# 24x16_RGB_Top.net
KiCad netlist of a schematic drawn in EAGLE
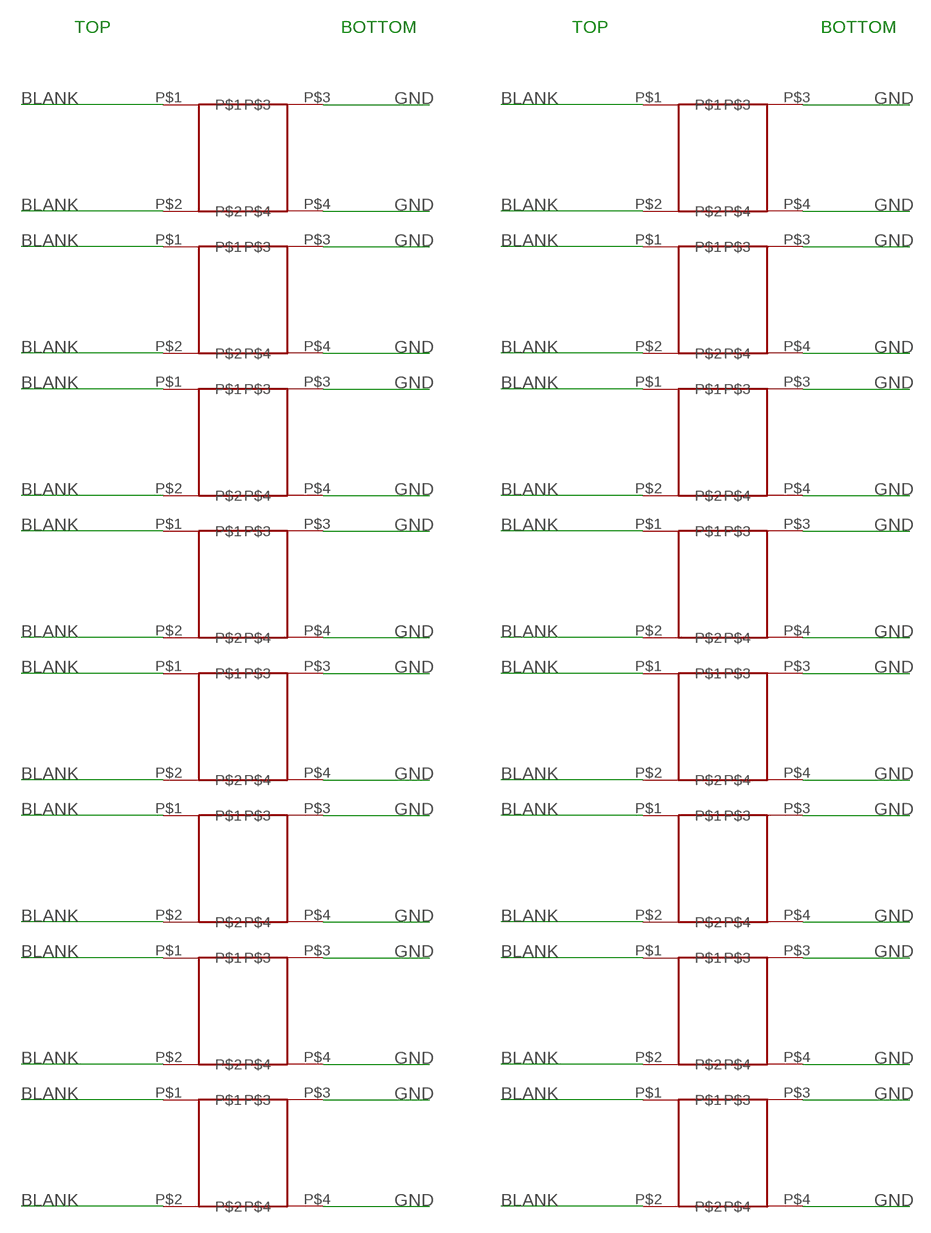
[diagram p0: schematic, sheet 1]
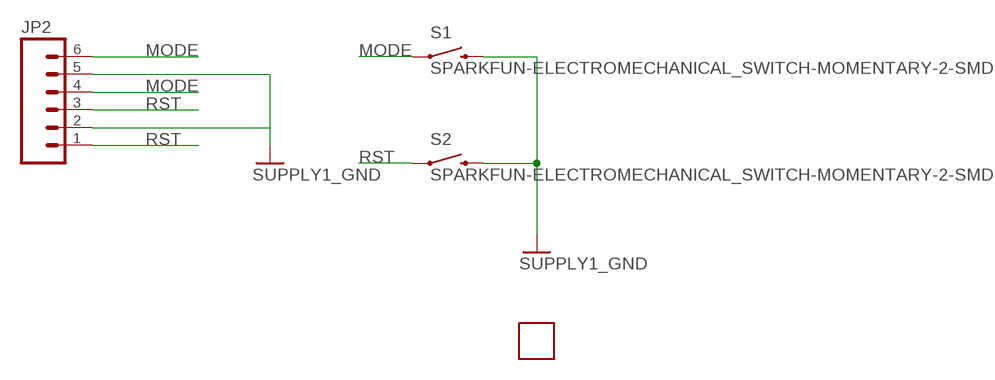
[diagram p1: schematic, sheet 2]

(export (version "E")
  (design (tool "Eeschema 10.0.6"))
  (components
    (comp (ref "SLOT1")
      (value "SLOT")
      (footprint "eagle-import:SLOT")
      (libsource (lib "eagle-import") (part "SLOT"))
    )
    (comp (ref "SLOT2")
      (value "SLOT")
      (footprint "eagle-import:SLOT")
      (libsource (lib "eagle-import") (part "SLOT"))
    )
    (comp (ref "SLOT3")
      (value "SLOT")
      (footprint "eagle-import:SLOT")
      (libsource (lib "eagle-import") (part "SLOT"))
    )
    (comp (ref "SLOT4")
      (value "SLOT")
      (footprint "eagle-import:SLOT")
      (libsource (lib "eagle-import") (part "SLOT"))
    )
    (comp (ref "SLOT5")
      (value "SLOT")
      (footprint "eagle-import:SLOT")
      (libsource (lib "eagle-import") (part "SLOT"))
    )
    (comp (ref "SLOT6")
      (value "SLOT")
      (footprint "eagle-import:SLOT")
      (libsource (lib "eagle-import") (part "SLOT"))
    )
    (comp (ref "SLOT7")
      (value "SLOT")
      (footprint "eagle-import:SLOT")
      (libsource (lib "eagle-import") (part "SLOT"))
    )
    (comp (ref "SLOT8")
      (value "SLOT")
      (footprint "eagle-import:SLOT")
      (libsource (lib "eagle-import") (part "SLOT"))
    )
    (comp (ref "SLOT9")
      (value "SLOT")
      (footprint "eagle-import:SLOT")
      (libsource (lib "eagle-import") (part "SLOT"))
    )
    (comp (ref "SLOT10")
      (value "SLOT")
      (footprint "eagle-import:SLOT")
      (libsource (lib "eagle-import") (part "SLOT"))
    )
    (comp (ref "SLOT11")
      (value "SLOT")
      (footprint "eagle-import:SLOT")
      (libsource (lib "eagle-import") (part "SLOT"))
    )
    (comp (ref "SLOT12")
      (value "SLOT")
      (footprint "eagle-import:SLOT")
      (libsource (lib "eagle-import") (part "SLOT"))
    )
    (comp (ref "SLOT13")
      (value "SLOT")
      (footprint "eagle-import:SLOT")
      (libsource (lib "eagle-import") (part "SLOT"))
    )
    (comp (ref "SLOT14")
      (value "SLOT")
      (footprint "eagle-import:SLOT")
      (libsource (lib "eagle-import") (part "SLOT"))
    )
    (comp (ref "SLOT15")
      (value "SLOT")
      (footprint "eagle-import:SLOT")
      (libsource (lib "eagle-import") (part "SLOT"))
    )
    (comp (ref "SLOT16")
      (value "SLOT")
      (footprint "eagle-import:SLOT")
      (libsource (lib "eagle-import") (part "SLOT"))
    )
    (comp (ref "JP2")
      (value "M06SIP")
      (footprint "eagle-import:1X06")
      (libsource (lib "eagle-import") (part "M06SIP"))
    )
    (comp (ref "S1")
      (value "SPARKFUN-ELECTROMECHANICAL_SWITCH-MOMENTARY-2-SMD-1101NE")
      (footprint "eagle-import:SPARKFUN-ELECTROMECHANICAL_TACTILE-SWITCH-1101NE")
      (libsource (lib "eagle-import") (part "SPARKFUN-ELECTROMECHANICAL_SWITCH-MOMENTARY-2-SMD-1101NE"))
    )
    (comp (ref "S2")
      (value "SPARKFUN-ELECTROMECHANICAL_SWITCH-MOMENTARY-2-SMD-1101NE")
      (footprint "eagle-import:SPARKFUN-ELECTROMECHANICAL_TACTILE-SWITCH-1101NE")
      (libsource (lib "eagle-import") (part "SPARKFUN-ELECTROMECHANICAL_SWITCH-MOMENTARY-2-SMD-1101NE"))
    )
    (comp (ref "U$1")
      (value "USB_PANNEL")
      (footprint "eagle-import:USB_PANNEL")
      (libsource (lib "eagle-import") (part "USB_PANNEL"))
    )
  )
  (nets
    (net (code "1") (name "BLANK") (class "Default")
      (node (ref "SLOT1") (pin "P$1") (pinfunction "P$1_P$1") (pintype "bidirectional"))
      (node (ref "SLOT1") (pin "P$2") (pinfunction "P$2_P$2") (pintype "bidirectional"))
      (node (ref "SLOT10") (pin "P$1") (pinfunction "P$1_P$1") (pintype "bidirectional"))
      (node (ref "SLOT10") (pin "P$2") (pinfunction "P$2_P$2") (pintype "bidirectional"))
      (node (ref "SLOT11") (pin "P$1") (pinfunction "P$1_P$1") (pintype "bidirectional"))
      (node (ref "SLOT11") (pin "P$2") (pinfunction "P$2_P$2") (pintype "bidirectional"))
      (node (ref "SLOT12") (pin "P$1") (pinfunction "P$1_P$1") (pintype "bidirectional"))
      (node (ref "SLOT12") (pin "P$2") (pinfunction "P$2_P$2") (pintype "bidirectional"))
      (node (ref "SLOT13") (pin "P$1") (pinfunction "P$1_P$1") (pintype "bidirectional"))
      (node (ref "SLOT13") (pin "P$2") (pinfunction "P$2_P$2") (pintype "bidirectional"))
      (node (ref "SLOT14") (pin "P$1") (pinfunction "P$1_P$1") (pintype "bidirectional"))
      (node (ref "SLOT14") (pin "P$2") (pinfunction "P$2_P$2") (pintype "bidirectional"))
      (node (ref "SLOT15") (pin "P$1") (pinfunction "P$1_P$1") (pintype "bidirectional"))
      (node (ref "SLOT15") (pin "P$2") (pinfunction "P$2_P$2") (pintype "bidirectional"))
      (node (ref "SLOT16") (pin "P$1") (pinfunction "P$1_P$1") (pintype "bidirectional"))
      (node (ref "SLOT16") (pin "P$2") (pinfunction "P$2_P$2") (pintype "bidirectional"))
      (node (ref "SLOT2") (pin "P$1") (pinfunction "P$1_P$1") (pintype "bidirectional"))
      (node (ref "SLOT2") (pin "P$2") (pinfunction "P$2_P$2") (pintype "bidirectional"))
      (node (ref "SLOT3") (pin "P$1") (pinfunction "P$1_P$1") (pintype "bidirectional"))
      (node (ref "SLOT3") (pin "P$2") (pinfunction "P$2_P$2") (pintype "bidirectional"))
      (node (ref "SLOT4") (pin "P$1") (pinfunction "P$1_P$1") (pintype "bidirectional"))
      (node (ref "SLOT4") (pin "P$2") (pinfunction "P$2_P$2") (pintype "bidirectional"))
      (node (ref "SLOT5") (pin "P$1") (pinfunction "P$1_P$1") (pintype "bidirectional"))
      (node (ref "SLOT5") (pin "P$2") (pinfunction "P$2_P$2") (pintype "bidirectional"))
      (node (ref "SLOT6") (pin "P$1") (pinfunction "P$1_P$1") (pintype "bidirectional"))
      (node (ref "SLOT6") (pin "P$2") (pinfunction "P$2_P$2") (pintype "bidirectional"))
      (node (ref "SLOT7") (pin "P$1") (pinfunction "P$1_P$1") (pintype "bidirectional"))
      (node (ref "SLOT7") (pin "P$2") (pinfunction "P$2_P$2") (pintype "bidirectional"))
      (node (ref "SLOT8") (pin "P$1") (pinfunction "P$1_P$1") (pintype "bidirectional"))
      (node (ref "SLOT8") (pin "P$2") (pinfunction "P$2_P$2") (pintype "bidirectional"))
      (node (ref "SLOT9") (pin "P$1") (pinfunction "P$1_P$1") (pintype "bidirectional"))
      (node (ref "SLOT9") (pin "P$2") (pinfunction "P$2_P$2") (pintype "bidirectional"))
    )
    (net (code "2") (name "GND") (class "Default")
      (node (ref "JP2") (pin "2") (pinfunction "2_2") (pintype "passive"))
      (node (ref "JP2") (pin "5") (pinfunction "5_5") (pintype "passive"))
      (node (ref "S1") (pin "P$2") (pinfunction "2_P$2") (pintype "passive"))
      (node (ref "S2") (pin "P$2") (pinfunction "2_P$2") (pintype "passive"))
      (node (ref "SLOT1") (pin "P$3") (pinfunction "P$3_P$3") (pintype "bidirectional"))
      (node (ref "SLOT1") (pin "P$4") (pinfunction "P$4_P$4") (pintype "bidirectional"))
      (node (ref "SLOT10") (pin "P$3") (pinfunction "P$3_P$3") (pintype "bidirectional"))
      (node (ref "SLOT10") (pin "P$4") (pinfunction "P$4_P$4") (pintype "bidirectional"))
      (node (ref "SLOT11") (pin "P$3") (pinfunction "P$3_P$3") (pintype "bidirectional"))
      (node (ref "SLOT11") (pin "P$4") (pinfunction "P$4_P$4") (pintype "bidirectional"))
      (node (ref "SLOT12") (pin "P$3") (pinfunction "P$3_P$3") (pintype "bidirectional"))
      (node (ref "SLOT12") (pin "P$4") (pinfunction "P$4_P$4") (pintype "bidirectional"))
      (node (ref "SLOT13") (pin "P$3") (pinfunction "P$3_P$3") (pintype "bidirectional"))
      (node (ref "SLOT13") (pin "P$4") (pinfunction "P$4_P$4") (pintype "bidirectional"))
      (node (ref "SLOT14") (pin "P$3") (pinfunction "P$3_P$3") (pintype "bidirectional"))
      (node (ref "SLOT14") (pin "P$4") (pinfunction "P$4_P$4") (pintype "bidirectional"))
      (node (ref "SLOT15") (pin "P$3") (pinfunction "P$3_P$3") (pintype "bidirectional"))
      (node (ref "SLOT15") (pin "P$4") (pinfunction "P$4_P$4") (pintype "bidirectional"))
      (node (ref "SLOT16") (pin "P$3") (pinfunction "P$3_P$3") (pintype "bidirectional"))
      (node (ref "SLOT16") (pin "P$4") (pinfunction "P$4_P$4") (pintype "bidirectional"))
      (node (ref "SLOT2") (pin "P$3") (pinfunction "P$3_P$3") (pintype "bidirectional"))
      (node (ref "SLOT2") (pin "P$4") (pinfunction "P$4_P$4") (pintype "bidirectional"))
      (node (ref "SLOT3") (pin "P$3") (pinfunction "P$3_P$3") (pintype "bidirectional"))
      (node (ref "SLOT3") (pin "P$4") (pinfunction "P$4_P$4") (pintype "bidirectional"))
      (node (ref "SLOT4") (pin "P$3") (pinfunction "P$3_P$3") (pintype "bidirectional"))
      (node (ref "SLOT4") (pin "P$4") (pinfunction "P$4_P$4") (pintype "bidirectional"))
      (node (ref "SLOT5") (pin "P$3") (pinfunction "P$3_P$3") (pintype "bidirectional"))
      (node (ref "SLOT5") (pin "P$4") (pinfunction "P$4_P$4") (pintype "bidirectional"))
      (node (ref "SLOT6") (pin "P$3") (pinfunction "P$3_P$3") (pintype "bidirectional"))
      (node (ref "SLOT6") (pin "P$4") (pinfunction "P$4_P$4") (pintype "bidirectional"))
      (node (ref "SLOT7") (pin "P$3") (pinfunction "P$3_P$3") (pintype "bidirectional"))
      (node (ref "SLOT7") (pin "P$4") (pinfunction "P$4_P$4") (pintype "bidirectional"))
      (node (ref "SLOT8") (pin "P$3") (pinfunction "P$3_P$3") (pintype "bidirectional"))
      (node (ref "SLOT8") (pin "P$4") (pinfunction "P$4_P$4") (pintype "bidirectional"))
      (node (ref "SLOT9") (pin "P$3") (pinfunction "P$3_P$3") (pintype "bidirectional"))
      (node (ref "SLOT9") (pin "P$4") (pinfunction "P$4_P$4") (pintype "bidirectional"))
    )
    (net (code "3") (name "MODE") (class "Default")
      (node (ref "JP2") (pin "4") (pinfunction "4_4") (pintype "passive"))
      (node (ref "JP2") (pin "6") (pinfunction "6_6") (pintype "passive"))
      (node (ref "S1") (pin "P$1") (pinfunction "1_P$1") (pintype "passive"))
    )
    (net (code "4") (name "RST") (class "Default")
      (node (ref "JP2") (pin "1") (pinfunction "1_1") (pintype "passive"))
      (node (ref "JP2") (pin "3") (pinfunction "3_3") (pintype "passive"))
      (node (ref "S2") (pin "P$1") (pinfunction "1_P$1") (pintype "passive"))
    )
  )
)
